# USBHeaders.net
KiCad netlist of a schematic drawn in Altium Designer
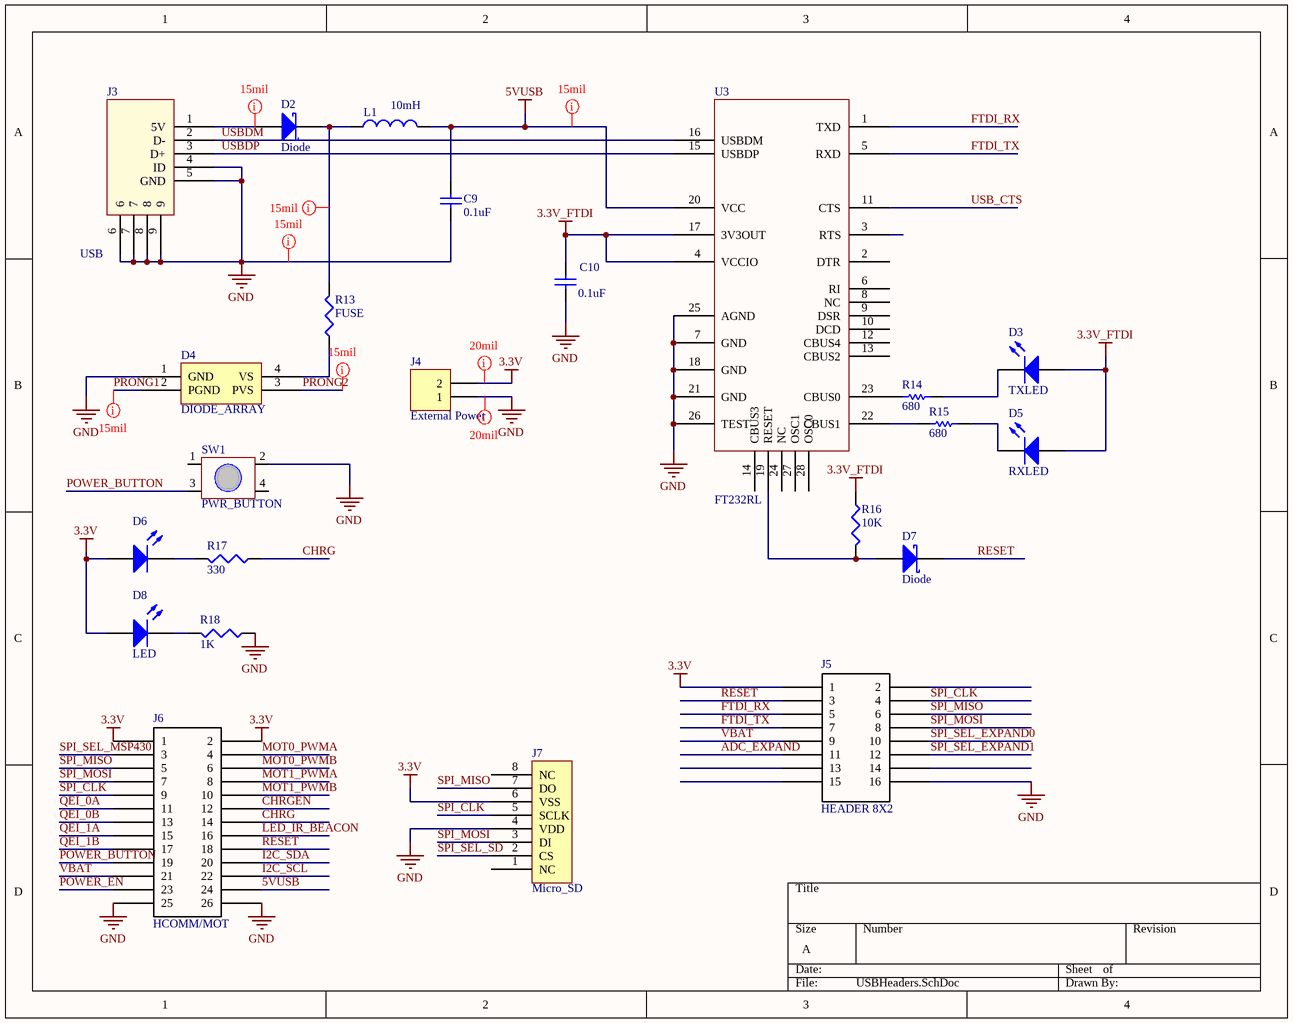
[diagram p0: USBHeaders.SchDoc]

(export (version "E")
  (design (tool "Eeschema 10.0.6"))
  (components
    (comp (ref "C9")
      (value "0.1uF")
      (footprint "CAPC1005L")
      (description "Capacitor")
      (fields (field (name "PUBLISHER") "Altium Limited"))
      (libsource (lib "Miscellaneous Devices") (part "Cap"))
    )
    (comp (ref "C10")
      (value "0.1uF")
      (footprint "CAPC1005L")
      (description "Capacitor")
      (fields (field (name "PUBLISHER") "Altium Limited"))
      (libsource (lib "Miscellaneous Devices") (part "Cap"))
    )
    (comp (ref "D2")
      (value "Diode")
      (footprint "SurfaceMount(603)")
      (libsource (lib "mrone") (part "SchottkeyDiode"))
    )
    (comp (ref "D3")
      (value "TXLED")
      (footprint "INDC2012L")
      (description "Typical RED, GREEN, YELLOW, AMBER GaAs LED")
      (fields (field (name "PUBLISHER") "Altium Limited"))
      (libsource (lib "Miscellaneous Devices") (part "LED2"))
    )
    (comp (ref "D4")
      (value "DIODE_ARRAY")
      (footprint "SOT143")
      (libsource (lib "mrone") (part "SCHOTTKEY_DIODE_ARRAY"))
    )
    (comp (ref "D5")
      (value "RXLED")
      (footprint "INDC2012L")
      (description "Typical RED, GREEN, YELLOW, AMBER GaAs LED")
      (fields (field (name "PUBLISHER") "Altium Limited"))
      (libsource (lib "Miscellaneous Devices") (part "LED2"))
    )
    (comp (ref "D6")
      (value "Charge")
      (footprint "INDC2012L")
      (description "Typical RED, GREEN, YELLOW, AMBER GaAs LED")
      (fields (field (name "PUBLISHER") "Altium Limited"))
      (libsource (lib "") (part "LED2_1"))
    )
    (comp (ref "D7")
      (value "Diode")
      (footprint "SurfaceMount(603)")
      (libsource (lib "mrone") (part "SchottkeyDiode"))
    )
    (comp (ref "D8") (value "LED") (footprint "SurfaceMount(603)") (libsource (lib "mrone") (part "LED")))
    (comp (ref "J3")
      (value "USB")
      (footprint "USB Minib (thru-hole)")
      (libsource (lib "mrone") (part "USB-ConnTH"))
    )
    (comp (ref "J4")
      (value "External Power")
      (footprint "HDR1X2")
      (description "Header, 2-Pin")
      (fields (field (name "PUBLISHER") "Altium Limited"))
      (libsource (lib "Miscellaneous Connectors") (part "Header 2"))
    )
    (comp (ref "J5")
      (value "HEADER 8X2")
      (footprint "HEADERSM 8X2")
      (libsource (lib "mrone") (part "HEADERS 8X2"))
    )
    (comp (ref "J6")
      (value "HCOMM/MOT")
      (footprint "HeaderSM 13x2")
      (description "Header, 2X20, 50mil, IDC")
      (libsource (lib "mrone") (part "HCOMM/HMOT"))
    )
    (comp (ref "J7") (value "Micro_SD") (footprint "MICRO_SD") (libsource (lib "mrone") (part "MICRO_SD")))
    (comp (ref "L1")
      (value "10mH")
      (footprint "INDC2012L")
      (description "Inductor")
      (fields (field (name "PUBLISHER") "Altium Limited"))
      (libsource (lib "Miscellaneous Devices") (part "Inductor"))
    )
    (comp (ref "R13")
      (value "FUSE")
      (footprint "RESC3225L")
      (description "Resistor")
      (fields (field (name "Comment") "Res3") (field (name "PUBLISHER") "Altium Limited"))
      (libsource (lib "Miscellaneous Devices") (part "Res3"))
    )
    (comp (ref "R14")
      (value "680")
      (footprint "RESC1608L")
      (description "Resistor")
      (fields (field (name "PUBLISHER") "Altium Limited"))
      (libsource (lib "Miscellaneous Devices") (part "Res1"))
    )
    (comp (ref "R15")
      (value "680")
      (footprint "RESC1608L")
      (description "Resistor")
      (fields (field (name "PUBLISHER") "Altium Limited"))
      (libsource (lib "Miscellaneous Devices") (part "Res1"))
    )
    (comp (ref "R16")
      (value "10K")
      (footprint "RESC1608L")
      (description "Resistor")
      (fields (field (name "Comment") "Res3") (field (name "PUBLISHER") "Altium Limited"))
      (libsource (lib "Miscellaneous Devices") (part "Res3"))
    )
    (comp (ref "R17")
      (value "330")
      (footprint "RESC1608L")
      (description "Resistor")
      (fields (field (name "Comment") "Res3") (field (name "PUBLISHER") "Altium Limited"))
      (libsource (lib "Miscellaneous Devices") (part "Res3"))
    )
    (comp (ref "R18")
      (value "1K")
      (footprint "RESC1608L")
      (description "Resistor")
      (fields (field (name "Comment") "Res3") (field (name "PUBLISHER") "Altium Limited"))
      (libsource (lib "Miscellaneous Devices") (part "Res3"))
    )
    (comp (ref "SW1")
      (value "PWR_BUTTON")
      (footprint "SwitchTall-TL330")
      (libsource (lib "mrone") (part "Switch-TL330"))
    )
    (comp (ref "U3") (value "FT232RL") (footprint "SSOP-28") (libsource (lib "mrone") (part "FT232RL")))
  )
  (nets
    (net (code "2") (name "/ADC_EXPAND") (class "Default")
      (node (ref "J5") (pin "11") (pinfunction "11_11") (pintype "passive"))
    )
    (net (code "3") (name "/CHRG") (class "Default")
      (node (ref "J6") (pin "14") (pinfunction "14_14") (pintype "passive"))
      (node (ref "R17") (pin "1") (pinfunction "1_1") (pintype "passive"))
    )
    (net (code "4") (name "/CHRGEN") (class "Default")
      (node (ref "J6") (pin "12") (pinfunction "12_12") (pintype "passive"))
    )
    (net (code "5") (name "/FTDI_RX") (class "Default")
      (node (ref "J5") (pin "5") (pinfunction "5_5") (pintype "passive"))
      (node (ref "U3") (pin "1") (pinfunction "TXD_1") (pintype "passive"))
    )
    (net (code "6") (name "/FTDI_TX") (class "Default")
      (node (ref "J5") (pin "7") (pinfunction "7_7") (pintype "passive"))
      (node (ref "U3") (pin "5") (pinfunction "RXD_5") (pintype "passive"))
    )
    (net (code "7") (name "/I2C_SCL") (class "Default")
      (node (ref "J6") (pin "22") (pinfunction "22_22") (pintype "passive"))
    )
    (net (code "8") (name "/I2C_SDA") (class "Default")
      (node (ref "J6") (pin "20") (pinfunction "20_20") (pintype "passive"))
    )
    (net (code "9") (name "/LED_IR_BEACON") (class "Default")
      (node (ref "J6") (pin "16") (pinfunction "16_16") (pintype "passive"))
    )
    (net (code "10") (name "/MOT0_PWMA") (class "Default")
      (node (ref "J6") (pin "4") (pinfunction "4_4") (pintype "passive"))
    )
    (net (code "11") (name "/MOT0_PWMB") (class "Default")
      (node (ref "J6") (pin "6") (pinfunction "6_6") (pintype "passive"))
    )
    (net (code "12") (name "/MOT1_PWMA") (class "Default")
      (node (ref "J6") (pin "8") (pinfunction "8_8") (pintype "passive"))
    )
    (net (code "13") (name "/MOT1_PWMB") (class "Default")
      (node (ref "J6") (pin "10") (pinfunction "10_10") (pintype "passive"))
    )
    (net (code "14") (name "/POWER_BUTTON") (class "Default")
      (node (ref "J6") (pin "19") (pinfunction "19_19") (pintype "passive"))
      (node (ref "SW1") (pin "3") (pinfunction "3_3") (pintype "passive"))
    )
    (net (code "15") (name "/POWER_EN") (class "Default")
      (node (ref "J6") (pin "23") (pinfunction "23_23") (pintype "passive"))
    )
    (net (code "16") (name "/PRONG1") (class "Default")
      (node (ref "D4") (pin "2") (pinfunction "PGND_2") (pintype "passive"))
    )
    (net (code "17") (name "/PRONG2") (class "Default")
      (node (ref "D4") (pin "3") (pinfunction "PVS_3") (pintype "passive"))
    )
    (net (code "18") (name "/QEI_0A") (class "Default")
      (node (ref "J6") (pin "11") (pinfunction "11_11") (pintype "passive"))
    )
    (net (code "19") (name "/QEI_0B") (class "Default")
      (node (ref "J6") (pin "13") (pinfunction "13_13") (pintype "passive"))
    )
    (net (code "20") (name "/QEI_1A") (class "Default")
      (node (ref "J6") (pin "15") (pinfunction "15_15") (pintype "passive"))
    )
    (net (code "21") (name "/QEI_1B") (class "Default")
      (node (ref "J6") (pin "17") (pinfunction "17_17") (pintype "passive"))
    )
    (net (code "22") (name "/RESET") (class "Default")
      (node (ref "D7") (pin "1") (pinfunction "K_1") (pintype "passive"))
      (node (ref "J5") (pin "3") (pinfunction "3_3") (pintype "passive"))
      (node (ref "J6") (pin "18") (pinfunction "18_18") (pintype "passive"))
    )
    (net (code "23") (name "/SPI_CLK") (class "Default")
      (node (ref "J5") (pin "4") (pinfunction "4_4") (pintype "passive"))
      (node (ref "J6") (pin "9") (pinfunction "9_9") (pintype "passive"))
      (node (ref "J7") (pin "5") (pinfunction "SCLK_5") (pintype "passive"))
    )
    (net (code "24") (name "/SPI_MISO") (class "Default")
      (node (ref "J5") (pin "6") (pinfunction "6_6") (pintype "passive"))
      (node (ref "J6") (pin "5") (pinfunction "5_5") (pintype "passive"))
      (node (ref "J7") (pin "7") (pinfunction "DO_7") (pintype "passive"))
    )
    (net (code "25") (name "/SPI_MOSI") (class "Default")
      (node (ref "J5") (pin "8") (pinfunction "8_8") (pintype "passive"))
      (node (ref "J6") (pin "7") (pinfunction "7_7") (pintype "passive"))
      (node (ref "J7") (pin "3") (pinfunction "DI_3") (pintype "passive"))
    )
    (net (code "26") (name "/SPI_SEL_EXPAND0") (class "Default")
      (node (ref "J5") (pin "10") (pinfunction "10_10") (pintype "passive"))
    )
    (net (code "27") (name "/SPI_SEL_EXPAND1") (class "Default")
      (node (ref "J5") (pin "12") (pinfunction "12_12") (pintype "passive"))
    )
    (net (code "28") (name "/SPI_SEL_MSP430") (class "Default")
      (node (ref "J6") (pin "3") (pinfunction "3_3") (pintype "passive"))
    )
    (net (code "29") (name "/SPI_SEL_SD") (class "Default")
      (node (ref "J7") (pin "2") (pinfunction "CS_2") (pintype "passive"))
    )
    (net (code "30") (name "/USBDM") (class "Default")
      (node (ref "J3") (pin "2") (pinfunction "D-_2") (pintype "passive"))
      (node (ref "U3") (pin "16") (pinfunction "USBDM_16") (pintype "passive"))
    )
    (net (code "31") (name "/USBDP") (class "Default")
      (node (ref "J3") (pin "3") (pinfunction "D+_3") (pintype "passive"))
      (node (ref "U3") (pin "15") (pinfunction "USBDP_15") (pintype "passive"))
    )
    (net (code "32") (name "/USB_CTS") (class "Default")
      (node (ref "U3") (pin "11") (pinfunction "CTS_11") (pintype "passive"))
    )
    (net (code "33") (name "/VBAT") (class "Default")
      (node (ref "J5") (pin "9") (pinfunction "9_9") (pintype "passive"))
      (node (ref "J6") (pin "21") (pinfunction "21_21") (pintype "passive"))
    )
    (net (code "34") (name "3.3V") (class "Default")
      (node (ref "D6") (pin "1") (pinfunction "A_1") (pintype "passive"))
      (node (ref "D8") (pin "1") (pinfunction "A_1") (pintype "passive"))
      (node (ref "J4") (pin "2") (pinfunction "2_2") (pintype "passive"))
      (node (ref "J5") (pin "1") (pinfunction "1_1") (pintype "passive"))
      (node (ref "J6") (pin "1") (pinfunction "1_1") (pintype "passive"))
      (node (ref "J6") (pin "2") (pinfunction "2_2") (pintype "passive"))
      (node (ref "J7") (pin "6") (pinfunction "VSS_6") (pintype "passive"))
    )
    (net (code "35") (name "3.3V_FTDI") (class "Default")
      (node (ref "C10") (pin "2") (pinfunction "2_2") (pintype "passive"))
      (node (ref "D3") (pin "1") (pinfunction "A_1") (pintype "passive"))
      (node (ref "D5") (pin "1") (pinfunction "A_1") (pintype "passive"))
      (node (ref "R16") (pin "1") (pinfunction "1_1") (pintype "passive"))
      (node (ref "U3") (pin "17") (pinfunction "3V3OUT_17") (pintype "passive"))
      (node (ref "U3") (pin "4") (pinfunction "VCCIO_4") (pintype "passive"))
    )
    (net (code "36") (name "5VUSB") (class "Default")
      (node (ref "C9") (pin "2") (pinfunction "2_2") (pintype "passive"))
      (node (ref "J6") (pin "24") (pinfunction "24_24") (pintype "passive"))
      (node (ref "L1") (pin "2") (pinfunction "2_2") (pintype "passive"))
      (node (ref "U3") (pin "20") (pinfunction "VCC_20") (pintype "passive"))
    )
    (net (code "37") (name "GND") (class "Default")
      (node (ref "C10") (pin "1") (pinfunction "1_1") (pintype "passive"))
      (node (ref "C9") (pin "1") (pinfunction "1_1") (pintype "passive"))
      (node (ref "D4") (pin "1") (pinfunction "GND_1") (pintype "passive"))
      (node (ref "J3") (pin "4") (pinfunction "ID_4") (pintype "passive"))
      (node (ref "J3") (pin "5") (pinfunction "GND_5") (pintype "passive"))
      (node (ref "J3") (pin "6") (pinfunction "6_6") (pintype "passive"))
      (node (ref "J3") (pin "7") (pinfunction "7_7") (pintype "passive"))
      (node (ref "J3") (pin "8") (pinfunction "8_8") (pintype "passive"))
      (node (ref "J3") (pin "9") (pinfunction "9_9") (pintype "passive"))
      (node (ref "J4") (pin "1") (pinfunction "1_1") (pintype "passive"))
      (node (ref "J5") (pin "16") (pinfunction "16_16") (pintype "passive"))
      (node (ref "J6") (pin "25") (pinfunction "25_25") (pintype "passive"))
      (node (ref "J6") (pin "26") (pinfunction "26_26") (pintype "passive"))
      (node (ref "J7") (pin "4") (pinfunction "VDD_4") (pintype "passive"))
      (node (ref "R18") (pin "1") (pinfunction "1_1") (pintype "passive"))
      (node (ref "SW1") (pin "2") (pinfunction "2_2") (pintype "passive"))
      (node (ref "U3") (pin "18") (pinfunction "GND_18") (pintype "passive"))
      (node (ref "U3") (pin "21") (pinfunction "GND_21") (pintype "passive"))
      (node (ref "U3") (pin "25") (pinfunction "AGND_25") (pintype "passive"))
      (node (ref "U3") (pin "26") (pinfunction "TEST_26") (pintype "passive"))
      (node (ref "U3") (pin "7") (pinfunction "GND_7") (pintype "passive"))
    )
    (net (code "38") (name "Net-(D2-A)") (class "Default")
      (node (ref "D2") (pin "2") (pinfunction "A_2") (pintype "passive"))
      (node (ref "J3") (pin "1") (pinfunction "5V_1") (pintype "passive"))
    )
    (net (code "39") (name "Net-(D2-K)") (class "Default")
      (node (ref "D2") (pin "1") (pinfunction "K_1") (pintype "passive"))
      (node (ref "L1") (pin "1") (pinfunction "1_1") (pintype "passive"))
      (node (ref "R13") (pin "2") (pinfunction "2_2") (pintype "passive"))
    )
    (net (code "40") (name "Net-(D3-K)") (class "Default")
      (node (ref "D3") (pin "2") (pinfunction "K_2") (pintype "passive"))
      (node (ref "R14") (pin "2") (pinfunction "2_2") (pintype "passive"))
    )
    (net (code "41") (name "Net-(D4-VS)") (class "Default")
      (node (ref "D4") (pin "4") (pinfunction "VS_4") (pintype "passive"))
      (node (ref "R13") (pin "1") (pinfunction "1_1") (pintype "passive"))
    )
    (net (code "42") (name "Net-(D5-K)") (class "Default")
      (node (ref "D5") (pin "2") (pinfunction "K_2") (pintype "passive"))
      (node (ref "R15") (pin "2") (pinfunction "2_2") (pintype "passive"))
    )
    (net (code "43") (name "Net-(D6-K)") (class "Default")
      (node (ref "D6") (pin "2") (pinfunction "K_2") (pintype "passive"))
      (node (ref "R17") (pin "2") (pinfunction "2_2") (pintype "passive"))
    )
    (net (code "44") (name "Net-(D7-A)") (class "Default")
      (node (ref "D7") (pin "2") (pinfunction "A_2") (pintype "passive"))
      (node (ref "R16") (pin "2") (pinfunction "2_2") (pintype "passive"))
      (node (ref "U3") (pin "19") (pinfunction "RESET_19") (pintype "passive"))
    )
    (net (code "45") (name "Net-(D8-K)") (class "Default")
      (node (ref "D8") (pin "2") (pinfunction "K_2") (pintype "passive"))
      (node (ref "R18") (pin "2") (pinfunction "2_2") (pintype "passive"))
    )
    (net (code "46") (name "Net-(U3-CBUS0)") (class "Default")
      (node (ref "R14") (pin "1") (pinfunction "1_1") (pintype "passive"))
      (node (ref "U3") (pin "23") (pinfunction "CBUS0_23") (pintype "passive"))
    )
    (net (code "47") (name "Net-(U3-CBUS1)") (class "Default")
      (node (ref "R15") (pin "1") (pinfunction "1_1") (pintype "passive"))
      (node (ref "U3") (pin "22") (pinfunction "CBUS1_22") (pintype "passive"))
    )
    (net (code "48") (name "unconnected-(J5-Pad2)") (class "Default")
      (node (ref "J5") (pin "2") (pinfunction "2_2") (pintype "passive"))
    )
    (net (code "49") (name "unconnected-(J5-Pad13)") (class "Default")
      (node (ref "J5") (pin "13") (pinfunction "13_13") (pintype "passive"))
    )
    (net (code "50") (name "unconnected-(J5-Pad14)") (class "Default")
      (node (ref "J5") (pin "14") (pinfunction "14_14") (pintype "passive"))
    )
    (net (code "51") (name "unconnected-(J5-Pad15)") (class "Default")
      (node (ref "J5") (pin "15") (pinfunction "15_15") (pintype "passive"))
    )
    (net (code "52") (name "unconnected-(J7-NC-Pad1)") (class "Default")
      (node (ref "J7") (pin "1") (pinfunction "NC_1") (pintype "passive"))
    )
    (net (code "53") (name "unconnected-(J7-NC-Pad8)") (class "Default")
      (node (ref "J7") (pin "8") (pinfunction "NC_8") (pintype "passive"))
    )
    (net (code "54") (name "unconnected-(SW1-Pad1)") (class "Default")
      (node (ref "SW1") (pin "1") (pinfunction "1_1") (pintype "passive"))
    )
    (net (code "55") (name "unconnected-(SW1-Pad4)") (class "Default")
      (node (ref "SW1") (pin "4") (pinfunction "4_4") (pintype "passive"))
    )
    (net (code "56") (name "unconnected-(U3-CBUS2-Pad13)") (class "Default")
      (node (ref "U3") (pin "13") (pinfunction "CBUS2_13") (pintype "passive"))
    )
    (net (code "57") (name "unconnected-(U3-CBUS3-Pad14)") (class "Default")
      (node (ref "U3") (pin "14") (pinfunction "CBUS3_14") (pintype "passive"))
    )
    (net (code "58") (name "unconnected-(U3-CBUS4-Pad12)") (class "Default")
      (node (ref "U3") (pin "12") (pinfunction "CBUS4_12") (pintype "passive"))
    )
    (net (code "59") (name "unconnected-(U3-DCD-Pad10)") (class "Default")
      (node (ref "U3") (pin "10") (pinfunction "DCD_10") (pintype "passive"))
    )
    (net (code "60") (name "unconnected-(U3-DSR-Pad9)") (class "Default")
      (node (ref "U3") (pin "9") (pinfunction "DSR_9") (pintype "passive"))
    )
    (net (code "61") (name "unconnected-(U3-DTR-Pad2)") (class "Default")
      (node (ref "U3") (pin "2") (pinfunction "DTR_2") (pintype "passive"))
    )
    (net (code "62") (name "unconnected-(U3-NC-Pad8)") (class "Default")
      (node (ref "U3") (pin "8") (pinfunction "NC_8") (pintype "passive"))
    )
    (net (code "63") (name "unconnected-(U3-NC-Pad24)") (class "Default")
      (node (ref "U3") (pin "24") (pinfunction "NC_24") (pintype "passive"))
    )
    (net (code "64") (name "unconnected-(U3-OSC0-Pad28)") (class "Default")
      (node (ref "U3") (pin "28") (pinfunction "OSC0_28") (pintype "passive"))
    )
    (net (code "65") (name "unconnected-(U3-OSC1-Pad27)") (class "Default")
      (node (ref "U3") (pin "27") (pinfunction "OSC1_27") (pintype "passive"))
    )
    (net (code "66") (name "unconnected-(U3-RI-Pad6)") (class "Default")
      (node (ref "U3") (pin "6") (pinfunction "RI_6") (pintype "passive"))
    )
    (net (code "67") (name "unconnected-(U3-RTS-Pad3)") (class "Default")
      (node (ref "U3") (pin "3") (pinfunction "RTS_3") (pintype "passive"))
    )
  )
)
